# LV_Sensing.net
KiCad netlist of a schematic drawn in Altium Designer
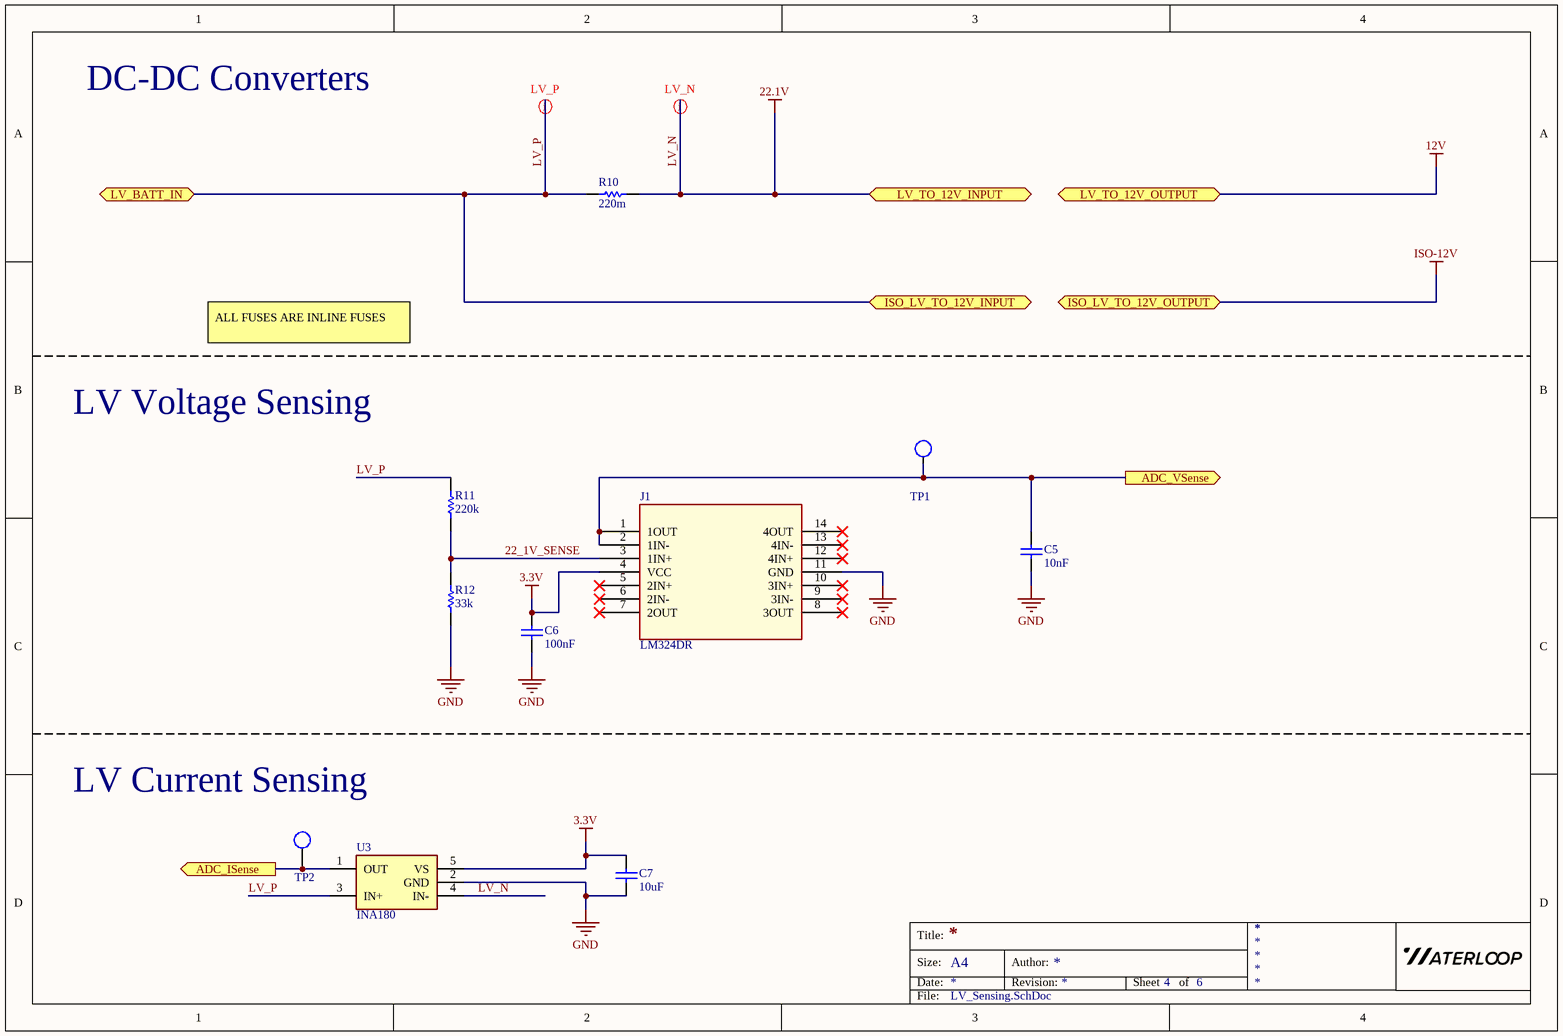
[diagram p0: LV_Sensing.SchDoc]

(export (version "E")
  (design (tool "Eeschema 10.0.6"))
  (components
    (comp (ref "C5")
      (value "10nF")
      (footprint "0603 - Capacitor")
      (description "Nonpolarized Capacitor")
      (fields (field (name "Comment") "Capacitor - Nonpolarized"))
      (libsource (lib "General") (part "Capacitor - Nonpolarized"))
    )
    (comp (ref "C6")
      (value "100nF")
      (footprint "0603 - Capacitor")
      (description "Nonpolarized Capacitor")
      (fields (field (name "Comment") "Capacitor - Nonpolarized"))
      (libsource (lib "General") (part "Capacitor - Nonpolarized"))
    )
    (comp (ref "C7")
      (value "10uF")
      (footprint "0603 - Capacitor")
      (description "Nonpolarized Capacitor")
      (fields (field (name "Comment") "Capacitor - Nonpolarized"))
      (libsource (lib "General") (part "Capacitor - Nonpolarized"))
    )
    (comp (ref "J1")
      (value "LM324DR")
      (footprint "LM324DR")
      (description "General Purpose Amplifier 4 Circuit 14-SOIC")
      (libsource (lib "GeneralComponents") (part "LM324DR"))
    )
    (comp (ref "R10")
      (value "220m")
      (footprint "2512 - RESISTOR")
      (description "Resistor")
      (libsource (lib "General") (part "Resistor"))
    )
    (comp (ref "R11")
      (value "220k")
      (footprint "0603 - Resistor")
      (description "Resistor")
      (libsource (lib "General") (part "Resistor"))
    )
    (comp (ref "R12")
      (value "33k")
      (footprint "0603 - Resistor")
      (description "Resistor")
      (libsource (lib "General") (part "Resistor"))
    )
    (comp (ref "TP1")
      (value "Test Point")
      (footprint "Test Point")
      (libsource (lib "General") (part "Test Point"))
    )
    (comp (ref "TP2")
      (value "Test Point")
      (footprint "Test Point")
      (libsource (lib "General") (part "Test Point"))
    )
    (comp (ref "U3")
      (value "INA180")
      (footprint "INA180")
      (description "0V to 26V Current Sense Amplifier")
      (fields
        (field (name "MANUFACTURER") "Texas Instruments")
        (field (name "MANUFACTURER PART NUMBER") "INA180A2IDBVR")
      )
      (libsource (lib "GeneralComponents") (part "INA180"))
    )
  )
  (nets
    (net (code "1") (name "/22_1V_SENSE") (class "Default")
      (node (ref "J1") (pin "3") (pinfunction "1IN+_3") (pintype "passive"))
      (node (ref "R11") (pin "2") (pinfunction "2_2") (pintype "passive"))
      (node (ref "R12") (pin "2") (pinfunction "2_2") (pintype "passive"))
    )
    (net (code "2") (name "/ADC_ISense") (class "Default")
      (node (ref "TP2") (pin "1") (pinfunction "0_1") (pintype "passive"))
      (node (ref "U3") (pin "1") (pinfunction "OUT_1") (pintype "passive"))
    )
    (net (code "3") (name "/ADC_VSense") (class "Default")
      (node (ref "C5") (pin "2") (pinfunction "2_2") (pintype "passive"))
      (node (ref "J1") (pin "1") (pinfunction "1OUT_1") (pintype "passive"))
      (node (ref "J1") (pin "2") (pinfunction "1IN-_2") (pintype "passive"))
      (node (ref "TP1") (pin "1") (pinfunction "0_1") (pintype "passive"))
    )
    (net (code "4") (name "/LV_P") (class "Default")
      (node (ref "R10") (pin "1") (pinfunction "1_1") (pintype "passive"))
      (node (ref "R11") (pin "1") (pinfunction "1_1") (pintype "passive"))
      (node (ref "U3") (pin "3") (pinfunction "IN+_3") (pintype "passive"))
    )
    (net (code "5") (name "3.3V") (class "Default")
      (node (ref "C6") (pin "2") (pinfunction "2_2") (pintype "passive"))
      (node (ref "C7") (pin "2") (pinfunction "2_2") (pintype "passive"))
      (node (ref "J1") (pin "4") (pinfunction "VCC_4") (pintype "power_in"))
      (node (ref "U3") (pin "5") (pinfunction "VS_5") (pintype "passive"))
    )
    (net (code "7") (name "22.1V") (class "Default")
      (node (ref "R10") (pin "2") (pinfunction "2_2") (pintype "passive"))
      (node (ref "U3") (pin "4") (pinfunction "IN-_4") (pintype "passive"))
    )
    (net (code "8") (name "GND") (class "Default")
      (node (ref "C5") (pin "1") (pinfunction "1_1") (pintype "passive"))
      (node (ref "C6") (pin "1") (pinfunction "1_1") (pintype "passive"))
      (node (ref "C7") (pin "1") (pinfunction "1_1") (pintype "passive"))
      (node (ref "J1") (pin "11") (pinfunction "GND_11") (pintype "power_in"))
      (node (ref "R12") (pin "1") (pinfunction "1_1") (pintype "passive"))
      (node (ref "U3") (pin "2") (pinfunction "GND_2") (pintype "passive"))
    )
    (net (code "10") (name "unconnected-(J1-2IN+-Pad5)") (class "Default")
      (node (ref "J1") (pin "5") (pinfunction "2IN+_5") (pintype "passive+no_connect"))
    )
    (net (code "11") (name "unconnected-(J1-2IN--Pad6)") (class "Default")
      (node (ref "J1") (pin "6") (pinfunction "2IN-_6") (pintype "passive+no_connect"))
    )
    (net (code "12") (name "unconnected-(J1-2OUT-Pad7)") (class "Default")
      (node (ref "J1") (pin "7") (pinfunction "2OUT_7") (pintype "passive+no_connect"))
    )
    (net (code "13") (name "unconnected-(J1-3IN+-Pad10)") (class "Default")
      (node (ref "J1") (pin "10") (pinfunction "3IN+_10") (pintype "passive+no_connect"))
    )
    (net (code "14") (name "unconnected-(J1-3IN--Pad9)") (class "Default")
      (node (ref "J1") (pin "9") (pinfunction "3IN-_9") (pintype "passive+no_connect"))
    )
    (net (code "15") (name "unconnected-(J1-3OUT-Pad8)") (class "Default")
      (node (ref "J1") (pin "8") (pinfunction "3OUT_8") (pintype "passive+no_connect"))
    )
    (net (code "16") (name "unconnected-(J1-4IN+-Pad12)") (class "Default")
      (node (ref "J1") (pin "12") (pinfunction "4IN+_12") (pintype "passive+no_connect"))
    )
    (net (code "17") (name "unconnected-(J1-4IN--Pad13)") (class "Default")
      (node (ref "J1") (pin "13") (pinfunction "4IN-_13") (pintype "passive+no_connect"))
    )
    (net (code "18") (name "unconnected-(J1-4OUT-Pad14)") (class "Default")
      (node (ref "J1") (pin "14") (pinfunction "4OUT_14") (pintype "passive+no_connect"))
    )
  )
)
